# Conectores.net
KiCad netlist of a schematic drawn in Altium Designer
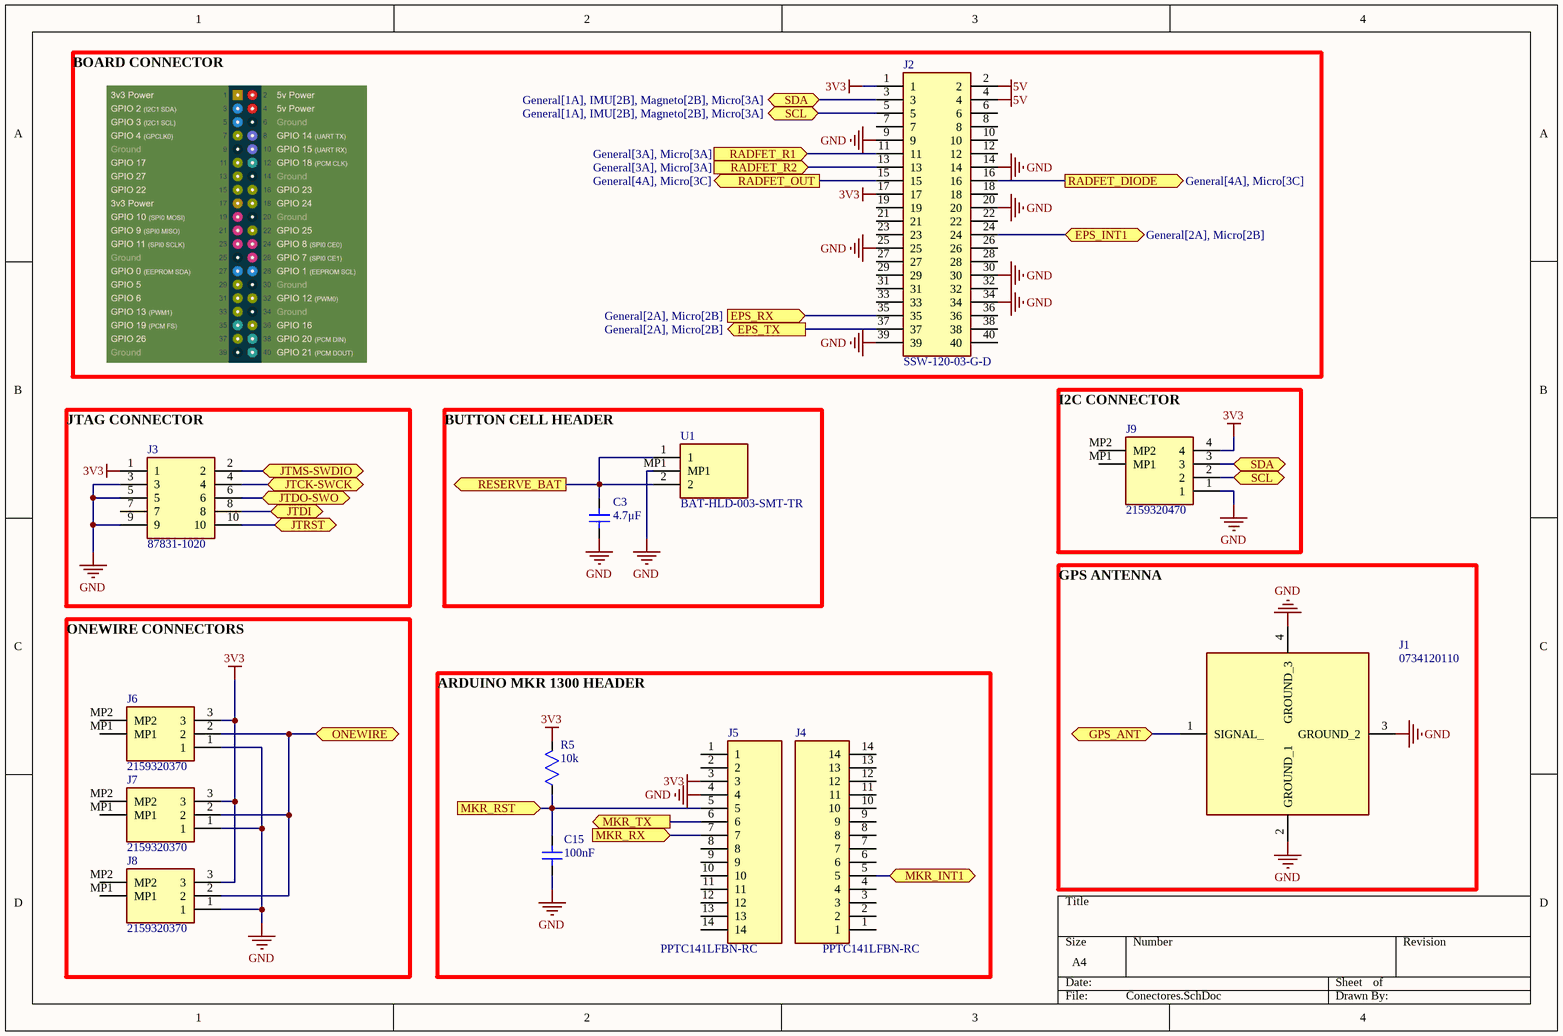
[diagram p0: Conectores.SchDoc]

(export (version "E")
  (design (tool "Eeschema 10.0.6"))
  (components
    (comp (ref "C3")
      (value "CAP_0805_1uF")
      (footprint "CAP SMD 0805")
      (description "Condensador 0805 1uF")
      (fields (field (name "VALOR") "4.7μF"))
      (libsource (lib "ARUS Electronica") (part "CAP_1206_2.2uF_100V"))
    )
    (comp (ref "C15")
      (value "CAP_0805_100nF")
      (footprint "CAP SMD 0805")
      (description "Condensador 0805 100nF")
      (fields (field (name "VALOR") "100nF"))
      (libsource (lib "ARUS Electronica") (part "CAP_0805_100nF"))
    )
    (comp (ref "J1")
      (value "0734120110")
      (footprint "SamacSys:0734120110")
      (description "Connector")
      (libsource (lib "*") (part "0734120110"))
    )
    (comp (ref "J2")
      (value "SSW-120-03-G-D")
      (footprint "SamacSys:RHDR40W79P254_2X20_5131X495X851P")
      (description "Connector")
      (fields (field (name "MOUSER PART NUMBER") "200-SSW12003GD"))
      (libsource (lib "*") (part "SSW-120-03-G-D"))
    )
    (comp (ref "J3")
      (value "87831-1020")
      (footprint "SHDR10W55P200_2X5_1265X630X640P")
      (fields (field (name "MOUSER PART NUMBER") "538-87831-1020"))
      (libsource (lib "ARUS Electronica") (part "87831-1020"))
    )
    (comp (ref "J4")
      (value "PPTC141LFBN-RC")
      (footprint "SamacSys:RHDR14W80P0X254_1X14_3606X254X850P")
      (description "Connector")
      (libsource (lib "") (part "PPTC141LFBN-RC_1"))
    )
    (comp (ref "J5")
      (value "PPTC141LFBN-RC")
      (footprint "SamacSys:RHDR14W80P0X254_1X14_3606X254X850P")
      (description "Connector")
      (libsource (lib "*") (part "PPTC141LFBN-RC"))
    )
    (comp (ref "J6")
      (value "2159320370")
      (footprint "SamacSys:2159320370")
      (description "Connector")
      (libsource (lib "*") (part "2159320370"))
    )
    (comp (ref "J7")
      (value "2159320370")
      (footprint "SamacSys:2159320370")
      (description "Connector")
      (libsource (lib "*") (part "2159320370"))
    )
    (comp (ref "J8")
      (value "2159320370")
      (footprint "SamacSys:2159320370")
      (description "Connector")
      (libsource (lib "*") (part "2159320370"))
    )
    (comp (ref "J9")
      (value "2159320470")
      (footprint "SamacSys:2159320470")
      (description "Connector")
      (libsource (lib "*") (part "2159320470"))
    )
    (comp (ref "R5")
      (value "RES_0805_10k")
      (footprint "RES SMD 0805")
      (description "Resistencia 0805 10k")
      (fields (field (name "VALOR") "10k"))
      (libsource (lib "ARUS Electronica") (part "RES_2512_22R_2W"))
    )
    (comp (ref "U1")
      (value "BAT-HLD-003-SMT-TR")
      (footprint "SamacSys:BATHLD003SMTTR")
      (description "Undefined or Miscellaneous")
      (fields (field (name "MOUSER PART NUMBER") "712-BAT-HLD-003SMTTR"))
      (libsource (lib "*") (part "BAT-HLD-003-SMT-TR"))
    )
  )
  (nets
    (net (code "1") (name "/EPS_INT1") (class "Default")
      (node (ref "J2") (pin "24") (pinfunction "24_24") (pintype "passive"))
    )
    (net (code "2") (name "/EPS_RX") (class "Default")
      (node (ref "J2") (pin "35") (pinfunction "35_35") (pintype "passive"))
    )
    (net (code "3") (name "/EPS_TX") (class "Default")
      (node (ref "J2") (pin "37") (pinfunction "37_37") (pintype "passive"))
    )
    (net (code "4") (name "/GPS_ANT") (class "Default")
      (node (ref "J1") (pin "1") (pinfunction "SIGNAL__1") (pintype "passive"))
    )
    (net (code "5") (name "/JTCK-SWCK") (class "Default")
      (node (ref "J3") (pin "4") (pinfunction "4_4") (pintype "passive"))
    )
    (net (code "6") (name "/JTDI") (class "Default")
      (node (ref "J3") (pin "8") (pinfunction "8_8") (pintype "passive"))
    )
    (net (code "7") (name "/JTDO-SWO") (class "Default")
      (node (ref "J3") (pin "6") (pinfunction "6_6") (pintype "passive"))
    )
    (net (code "8") (name "/JTMS-SWDIO") (class "Default")
      (node (ref "J3") (pin "2") (pinfunction "2_2") (pintype "passive"))
    )
    (net (code "9") (name "/JTRST") (class "Default")
      (node (ref "J3") (pin "10") (pinfunction "10_10") (pintype "passive"))
    )
    (net (code "10") (name "/MKR_INT1") (class "Default")
      (node (ref "J4") (pin "5") (pinfunction "5_5") (pintype "passive"))
    )
    (net (code "11") (name "/MKR_RST") (class "Default")
      (node (ref "C15") (pin "1") (pinfunction "1_1") (pintype "passive"))
      (node (ref "J5") (pin "5") (pinfunction "5_5") (pintype "passive"))
      (node (ref "R5") (pin "1") (pinfunction "1_1") (pintype "passive"))
    )
    (net (code "12") (name "/MKR_RX") (class "Default")
      (node (ref "J5") (pin "7") (pinfunction "7_7") (pintype "passive"))
    )
    (net (code "13") (name "/MKR_TX") (class "Default")
      (node (ref "J5") (pin "6") (pinfunction "6_6") (pintype "passive"))
    )
    (net (code "14") (name "/ONEWIRE") (class "Default")
      (node (ref "J6") (pin "2") (pinfunction "2_2") (pintype "passive"))
      (node (ref "J7") (pin "2") (pinfunction "2_2") (pintype "passive"))
      (node (ref "J8") (pin "2") (pinfunction "2_2") (pintype "passive"))
    )
    (net (code "15") (name "/RADFET_DIODE") (class "Default")
      (node (ref "J2") (pin "16") (pinfunction "16_16") (pintype "passive"))
    )
    (net (code "16") (name "/RADFET_OUT") (class "Default")
      (node (ref "J2") (pin "15") (pinfunction "15_15") (pintype "passive"))
    )
    (net (code "17") (name "/RADFET_R1") (class "Default")
      (node (ref "J2") (pin "11") (pinfunction "11_11") (pintype "passive"))
    )
    (net (code "18") (name "/RADFET_R2") (class "Default")
      (node (ref "J2") (pin "13") (pinfunction "13_13") (pintype "passive"))
    )
    (net (code "19") (name "/RESERVE_BAT") (class "Default")
      (node (ref "C3") (pin "1") (pinfunction "1_1") (pintype "passive"))
      (node (ref "U1") (pin "1") (pinfunction "1_1") (pintype "passive"))
      (node (ref "U1") (pin "2") (pinfunction "2_2") (pintype "passive"))
    )
    (net (code "20") (name "/SCL") (class "Default")
      (node (ref "J2") (pin "5") (pinfunction "5_5") (pintype "passive"))
      (node (ref "J9") (pin "2") (pinfunction "2_2") (pintype "passive"))
    )
    (net (code "21") (name "/SDA") (class "Default")
      (node (ref "J2") (pin "3") (pinfunction "3_3") (pintype "passive"))
      (node (ref "J9") (pin "3") (pinfunction "3_3") (pintype "passive"))
    )
    (net (code "22") (name "3V3") (class "Default")
      (node (ref "J2") (pin "1") (pinfunction "1_1") (pintype "passive"))
      (node (ref "J2") (pin "17") (pinfunction "17_17") (pintype "passive"))
      (node (ref "J3") (pin "1") (pinfunction "1_1") (pintype "passive"))
      (node (ref "J5") (pin "3") (pinfunction "3_3") (pintype "passive"))
      (node (ref "J6") (pin "3") (pinfunction "3_3") (pintype "passive"))
      (node (ref "J7") (pin "3") (pinfunction "3_3") (pintype "passive"))
      (node (ref "J8") (pin "3") (pinfunction "3_3") (pintype "passive"))
      (node (ref "J9") (pin "4") (pinfunction "4_4") (pintype "passive"))
      (node (ref "R5") (pin "2") (pinfunction "2_2") (pintype "passive"))
    )
    (net (code "23") (name "5V") (class "Default")
      (node (ref "J2") (pin "2") (pinfunction "2_2") (pintype "passive"))
      (node (ref "J2") (pin "4") (pinfunction "4_4") (pintype "passive"))
    )
    (net (code "24") (name "GND") (class "Default")
      (node (ref "C15") (pin "2") (pinfunction "2_2") (pintype "passive"))
      (node (ref "C3") (pin "2") (pinfunction "2_2") (pintype "passive"))
      (node (ref "J1") (pin "2") (pinfunction "GROUND_1_2") (pintype "passive"))
      (node (ref "J1") (pin "3") (pinfunction "GROUND_2_3") (pintype "passive"))
      (node (ref "J1") (pin "4") (pinfunction "GROUND_3_4") (pintype "passive"))
      (node (ref "J2") (pin "14") (pinfunction "14_14") (pintype "passive"))
      (node (ref "J2") (pin "20") (pinfunction "20_20") (pintype "passive"))
      (node (ref "J2") (pin "25") (pinfunction "25_25") (pintype "passive"))
      (node (ref "J2") (pin "30") (pinfunction "30_30") (pintype "passive"))
      (node (ref "J2") (pin "34") (pinfunction "34_34") (pintype "passive"))
      (node (ref "J2") (pin "39") (pinfunction "39_39") (pintype "passive"))
      (node (ref "J2") (pin "9") (pinfunction "9_9") (pintype "passive"))
      (node (ref "J3") (pin "3") (pinfunction "3_3") (pintype "passive"))
      (node (ref "J3") (pin "5") (pinfunction "5_5") (pintype "passive"))
      (node (ref "J3") (pin "9") (pinfunction "9_9") (pintype "passive"))
      (node (ref "J5") (pin "4") (pinfunction "4_4") (pintype "passive"))
      (node (ref "J6") (pin "1") (pinfunction "1_1") (pintype "passive"))
      (node (ref "J7") (pin "1") (pinfunction "1_1") (pintype "passive"))
      (node (ref "J8") (pin "1") (pinfunction "1_1") (pintype "passive"))
      (node (ref "J9") (pin "1") (pinfunction "1_1") (pintype "passive"))
      (node (ref "U1") (pin "MP1") (pinfunction "MP1_MP1") (pintype "passive"))
    )
    (net (code "25") (name "unconnected-(J2-Pad6)") (class "Default")
      (node (ref "J2") (pin "6") (pinfunction "6_6") (pintype "passive"))
    )
    (net (code "26") (name "unconnected-(J2-Pad7)") (class "Default")
      (node (ref "J2") (pin "7") (pinfunction "7_7") (pintype "passive"))
    )
    (net (code "27") (name "unconnected-(J2-Pad8)") (class "Default")
      (node (ref "J2") (pin "8") (pinfunction "8_8") (pintype "passive"))
    )
    (net (code "28") (name "unconnected-(J2-Pad10)") (class "Default")
      (node (ref "J2") (pin "10") (pinfunction "10_10") (pintype "passive"))
    )
    (net (code "29") (name "unconnected-(J2-Pad12)") (class "Default")
      (node (ref "J2") (pin "12") (pinfunction "12_12") (pintype "passive"))
    )
    (net (code "30") (name "unconnected-(J2-Pad18)") (class "Default")
      (node (ref "J2") (pin "18") (pinfunction "18_18") (pintype "passive"))
    )
    (net (code "31") (name "unconnected-(J2-Pad19)") (class "Default")
      (node (ref "J2") (pin "19") (pinfunction "19_19") (pintype "passive"))
    )
    (net (code "32") (name "unconnected-(J2-Pad21)") (class "Default")
      (node (ref "J2") (pin "21") (pinfunction "21_21") (pintype "passive"))
    )
    (net (code "33") (name "unconnected-(J2-Pad22)") (class "Default")
      (node (ref "J2") (pin "22") (pinfunction "22_22") (pintype "passive"))
    )
    (net (code "34") (name "unconnected-(J2-Pad23)") (class "Default")
      (node (ref "J2") (pin "23") (pinfunction "23_23") (pintype "passive"))
    )
    (net (code "35") (name "unconnected-(J2-Pad26)") (class "Default")
      (node (ref "J2") (pin "26") (pinfunction "26_26") (pintype "passive"))
    )
    (net (code "36") (name "unconnected-(J2-Pad27)") (class "Default")
      (node (ref "J2") (pin "27") (pinfunction "27_27") (pintype "passive"))
    )
    (net (code "37") (name "unconnected-(J2-Pad28)") (class "Default")
      (node (ref "J2") (pin "28") (pinfunction "28_28") (pintype "passive"))
    )
    (net (code "38") (name "unconnected-(J2-Pad29)") (class "Default")
      (node (ref "J2") (pin "29") (pinfunction "29_29") (pintype "passive"))
    )
    (net (code "39") (name "unconnected-(J2-Pad31)") (class "Default")
      (node (ref "J2") (pin "31") (pinfunction "31_31") (pintype "passive"))
    )
    (net (code "40") (name "unconnected-(J2-Pad32)") (class "Default")
      (node (ref "J2") (pin "32") (pinfunction "32_32") (pintype "passive"))
    )
    (net (code "41") (name "unconnected-(J2-Pad33)") (class "Default")
      (node (ref "J2") (pin "33") (pinfunction "33_33") (pintype "passive"))
    )
    (net (code "42") (name "unconnected-(J2-Pad36)") (class "Default")
      (node (ref "J2") (pin "36") (pinfunction "36_36") (pintype "passive"))
    )
    (net (code "43") (name "unconnected-(J2-Pad38)") (class "Default")
      (node (ref "J2") (pin "38") (pinfunction "38_38") (pintype "passive"))
    )
    (net (code "44") (name "unconnected-(J2-Pad40)") (class "Default")
      (node (ref "J2") (pin "40") (pinfunction "40_40") (pintype "passive"))
    )
    (net (code "45") (name "unconnected-(J3-Pad7)") (class "Default")
      (node (ref "J3") (pin "7") (pinfunction "7_7") (pintype "passive"))
    )
    (net (code "46") (name "unconnected-(J4-Pad1)") (class "Default")
      (node (ref "J4") (pin "1") (pinfunction "1_1") (pintype "passive"))
    )
    (net (code "47") (name "unconnected-(J4-Pad2)") (class "Default")
      (node (ref "J4") (pin "2") (pinfunction "2_2") (pintype "passive"))
    )
    (net (code "48") (name "unconnected-(J4-Pad3)") (class "Default")
      (node (ref "J4") (pin "3") (pinfunction "3_3") (pintype "passive"))
    )
    (net (code "49") (name "unconnected-(J4-Pad4)") (class "Default")
      (node (ref "J4") (pin "4") (pinfunction "4_4") (pintype "passive"))
    )
    (net (code "50") (name "unconnected-(J4-Pad6)") (class "Default")
      (node (ref "J4") (pin "6") (pinfunction "6_6") (pintype "passive"))
    )
    (net (code "51") (name "unconnected-(J4-Pad7)") (class "Default")
      (node (ref "J4") (pin "7") (pinfunction "7_7") (pintype "passive"))
    )
    (net (code "52") (name "unconnected-(J4-Pad8)") (class "Default")
      (node (ref "J4") (pin "8") (pinfunction "8_8") (pintype "passive"))
    )
    (net (code "53") (name "unconnected-(J4-Pad9)") (class "Default")
      (node (ref "J4") (pin "9") (pinfunction "9_9") (pintype "passive"))
    )
    (net (code "54") (name "unconnected-(J4-Pad10)") (class "Default")
      (node (ref "J4") (pin "10") (pinfunction "10_10") (pintype "passive"))
    )
    (net (code "55") (name "unconnected-(J4-Pad11)") (class "Default")
      (node (ref "J4") (pin "11") (pinfunction "11_11") (pintype "passive"))
    )
    (net (code "56") (name "unconnected-(J4-Pad12)") (class "Default")
      (node (ref "J4") (pin "12") (pinfunction "12_12") (pintype "passive"))
    )
    (net (code "57") (name "unconnected-(J4-Pad13)") (class "Default")
      (node (ref "J4") (pin "13") (pinfunction "13_13") (pintype "passive"))
    )
    (net (code "58") (name "unconnected-(J4-Pad14)") (class "Default")
      (node (ref "J4") (pin "14") (pinfunction "14_14") (pintype "passive"))
    )
    (net (code "59") (name "unconnected-(J5-Pad1)") (class "Default")
      (node (ref "J5") (pin "1") (pinfunction "1_1") (pintype "passive"))
    )
    (net (code "60") (name "unconnected-(J5-Pad2)") (class "Default")
      (node (ref "J5") (pin "2") (pinfunction "2_2") (pintype "passive"))
    )
    (net (code "61") (name "unconnected-(J5-Pad8)") (class "Default")
      (node (ref "J5") (pin "8") (pinfunction "8_8") (pintype "passive"))
    )
    (net (code "62") (name "unconnected-(J5-Pad9)") (class "Default")
      (node (ref "J5") (pin "9") (pinfunction "9_9") (pintype "passive"))
    )
    (net (code "63") (name "unconnected-(J5-Pad10)") (class "Default")
      (node (ref "J5") (pin "10") (pinfunction "10_10") (pintype "passive"))
    )
    (net (code "64") (name "unconnected-(J5-Pad11)") (class "Default")
      (node (ref "J5") (pin "11") (pinfunction "11_11") (pintype "passive"))
    )
    (net (code "65") (name "unconnected-(J5-Pad12)") (class "Default")
      (node (ref "J5") (pin "12") (pinfunction "12_12") (pintype "passive"))
    )
    (net (code "66") (name "unconnected-(J5-Pad13)") (class "Default")
      (node (ref "J5") (pin "13") (pinfunction "13_13") (pintype "passive"))
    )
    (net (code "67") (name "unconnected-(J5-Pad14)") (class "Default")
      (node (ref "J5") (pin "14") (pinfunction "14_14") (pintype "passive"))
    )
    (net (code "68") (name "unconnected-(J6-PadMP1)") (class "Default")
      (node (ref "J6") (pin "MP1") (pinfunction "MP1_MP1") (pintype "passive"))
    )
    (net (code "69") (name "unconnected-(J6-PadMP2)") (class "Default")
      (node (ref "J6") (pin "MP2") (pinfunction "MP2_MP2") (pintype "passive"))
    )
    (net (code "70") (name "unconnected-(J7-PadMP1)") (class "Default")
      (node (ref "J7") (pin "MP1") (pinfunction "MP1_MP1") (pintype "passive"))
    )
    (net (code "71") (name "unconnected-(J7-PadMP2)") (class "Default")
      (node (ref "J7") (pin "MP2") (pinfunction "MP2_MP2") (pintype "passive"))
    )
    (net (code "72") (name "unconnected-(J8-PadMP1)") (class "Default")
      (node (ref "J8") (pin "MP1") (pinfunction "MP1_MP1") (pintype "passive"))
    )
    (net (code "73") (name "unconnected-(J8-PadMP2)") (class "Default")
      (node (ref "J8") (pin "MP2") (pinfunction "MP2_MP2") (pintype "passive"))
    )
    (net (code "74") (name "unconnected-(J9-PadMP1)") (class "Default")
      (node (ref "J9") (pin "MP1") (pinfunction "MP1_MP1") (pintype "passive"))
    )
    (net (code "75") (name "unconnected-(J9-PadMP2)") (class "Default")
      (node (ref "J9") (pin "MP2") (pinfunction "MP2_MP2") (pintype "passive"))
    )
  )
)
